# Sheet1.net
KiCad netlist of a schematic drawn in Altium Designer
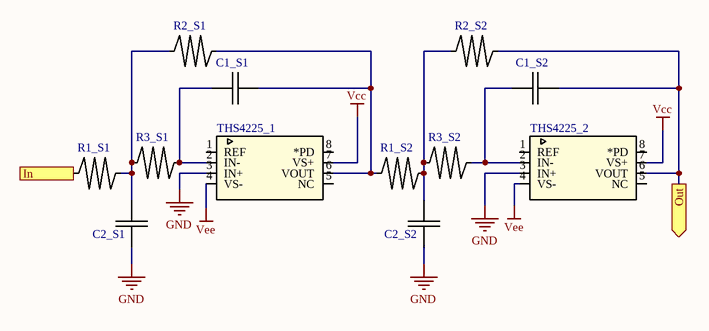
[diagram p0: Sheet1.SchDoc]

(export (version "E")
  (design (tool "Eeschema 10.0.6"))
  (components
    (comp (ref "C1_S1") (value "0603") (footprint "0603") (libsource (lib "Schlib1") (part "0603")))
    (comp (ref "C1_S2") (value "0603") (footprint "0603") (libsource (lib "Schlib1") (part "0603")))
    (comp (ref "C2_S1") (value "1885") (footprint "1885") (libsource (lib "Schlib1") (part "1885")))
    (comp (ref "C2_S2") (value "1885") (footprint "1885") (libsource (lib "Schlib1") (part "1885")))
    (comp (ref "R1_S1") (value "1206") (footprint "1206") (libsource (lib "Schlib1") (part "1206")))
    (comp (ref "R1_S2") (value "1206") (footprint "1206") (libsource (lib "Schlib1") (part "1206")))
    (comp (ref "R2_S1") (value "0402") (footprint "0402") (libsource (lib "Schlib1") (part "0402")))
    (comp (ref "R2_S2") (value "0402") (footprint "0402") (libsource (lib "Schlib1") (part "0402")))
    (comp (ref "R3_S1") (value "1206") (footprint "1206") (libsource (lib "Schlib1") (part "1206")))
    (comp (ref "R3_S2") (value "1206") (footprint "1206") (libsource (lib "Schlib1") (part "1206")))
    (comp (ref "THS4225_1")
      (value "THS4225DGK")
      (footprint "DGK8-M")
      (fields (field (name "COPYRIGHT") "Copyright (C) 2021 Ultra Librarian. All rights reserved."))
      (libsource (lib "Schlib1") (part "4225"))
    )
    (comp (ref "THS4225_2")
      (value "THS4225DGK")
      (footprint "DGK8-M")
      (fields (field (name "COPYRIGHT") "Copyright (C) 2021 Ultra Librarian. All rights reserved."))
      (libsource (lib "Schlib1") (part "4225"))
    )
  )
  (nets
    (net (code "1") (name "/In") (class "Default")
      (node (ref "R1_S1") (pin "1") (pinfunction "1_1") (pintype "passive"))
    )
    (net (code "2") (name "/Out") (class "Default")
      (node (ref "C1_S2") (pin "1") (pinfunction "1_1") (pintype "passive"))
      (node (ref "R2_S2") (pin "2") (pinfunction "2_2") (pintype "passive"))
      (node (ref "THS4225_2") (pin "6") (pinfunction "VOUT_6") (pintype "output"))
    )
    (net (code "3") (name "GND") (class "Default")
      (node (ref "C2_S1") (pin "2") (pinfunction "2_2") (pintype "passive"))
      (node (ref "C2_S2") (pin "2") (pinfunction "2_2") (pintype "passive"))
      (node (ref "THS4225_1") (pin "3") (pinfunction "IN+_3") (pintype "input"))
      (node (ref "THS4225_2") (pin "3") (pinfunction "IN+_3") (pintype "input"))
    )
    (net (code "4") (name "Net-(C2_S1-Pad1)") (class "Default")
      (node (ref "C2_S1") (pin "1") (pinfunction "1_1") (pintype "passive"))
      (node (ref "R1_S1") (pin "2") (pinfunction "2_2") (pintype "passive"))
      (node (ref "R2_S1") (pin "1") (pinfunction "1_1") (pintype "passive"))
      (node (ref "R3_S1") (pin "1") (pinfunction "1_1") (pintype "passive"))
    )
    (net (code "5") (name "Net-(C2_S2-Pad1)") (class "Default")
      (node (ref "C2_S2") (pin "1") (pinfunction "1_1") (pintype "passive"))
      (node (ref "R1_S2") (pin "2") (pinfunction "2_2") (pintype "passive"))
      (node (ref "R2_S2") (pin "1") (pinfunction "1_1") (pintype "passive"))
      (node (ref "R3_S2") (pin "1") (pinfunction "1_1") (pintype "passive"))
    )
    (net (code "6") (name "Net-(THS4225_1-IN-)") (class "Default")
      (node (ref "C1_S1") (pin "2") (pinfunction "2_2") (pintype "passive"))
      (node (ref "R3_S1") (pin "2") (pinfunction "2_2") (pintype "passive"))
      (node (ref "THS4225_1") (pin "2") (pinfunction "IN-_2") (pintype "input"))
    )
    (net (code "7") (name "Net-(THS4225_1-VOUT)") (class "Default")
      (node (ref "C1_S1") (pin "1") (pinfunction "1_1") (pintype "passive"))
      (node (ref "R1_S2") (pin "1") (pinfunction "1_1") (pintype "passive"))
      (node (ref "R2_S1") (pin "2") (pinfunction "2_2") (pintype "passive"))
      (node (ref "THS4225_1") (pin "6") (pinfunction "VOUT_6") (pintype "output"))
    )
    (net (code "8") (name "Net-(THS4225_2-IN-)") (class "Default")
      (node (ref "C1_S2") (pin "2") (pinfunction "2_2") (pintype "passive"))
      (node (ref "R3_S2") (pin "2") (pinfunction "2_2") (pintype "passive"))
      (node (ref "THS4225_2") (pin "2") (pinfunction "IN-_2") (pintype "input"))
    )
    (net (code "9") (name "Vcc") (class "Default")
      (node (ref "THS4225_1") (pin "7") (pinfunction "VS+_7") (pintype "power_in"))
      (node (ref "THS4225_2") (pin "7") (pinfunction "VS+_7") (pintype "power_in"))
    )
    (net (code "10") (name "Vee") (class "Default")
      (node (ref "THS4225_1") (pin "4") (pinfunction "VS-_4") (pintype "power_in"))
      (node (ref "THS4225_2") (pin "4") (pinfunction "VS-_4") (pintype "power_in"))
    )
    (net (code "11") (name "unconnected-(THS4225_1-*PD-Pad8)") (class "Default")
      (node (ref "THS4225_1") (pin "8") (pinfunction "*PD_8") (pintype "passive"))
    )
    (net (code "12") (name "unconnected-(THS4225_1-NC-Pad5)") (class "Default")
      (node (ref "THS4225_1") (pin "5") (pinfunction "NC_5") (pintype "passive"))
    )
    (net (code "13") (name "unconnected-(THS4225_1-REF-Pad1)") (class "Default")
      (node (ref "THS4225_1") (pin "1") (pinfunction "REF_1") (pintype "passive"))
    )
    (net (code "14") (name "unconnected-(THS4225_2-*PD-Pad8)") (class "Default")
      (node (ref "THS4225_2") (pin "8") (pinfunction "*PD_8") (pintype "passive"))
    )
    (net (code "15") (name "unconnected-(THS4225_2-NC-Pad5)") (class "Default")
      (node (ref "THS4225_2") (pin "5") (pinfunction "NC_5") (pintype "passive"))
    )
    (net (code "16") (name "unconnected-(THS4225_2-REF-Pad1)") (class "Default")
      (node (ref "THS4225_2") (pin "1") (pinfunction "REF_1") (pintype "passive"))
    )
  )
)
